# project3_PushButtonLedToggle.net
KiCad netlist of a schematic drawn in Altium Designer
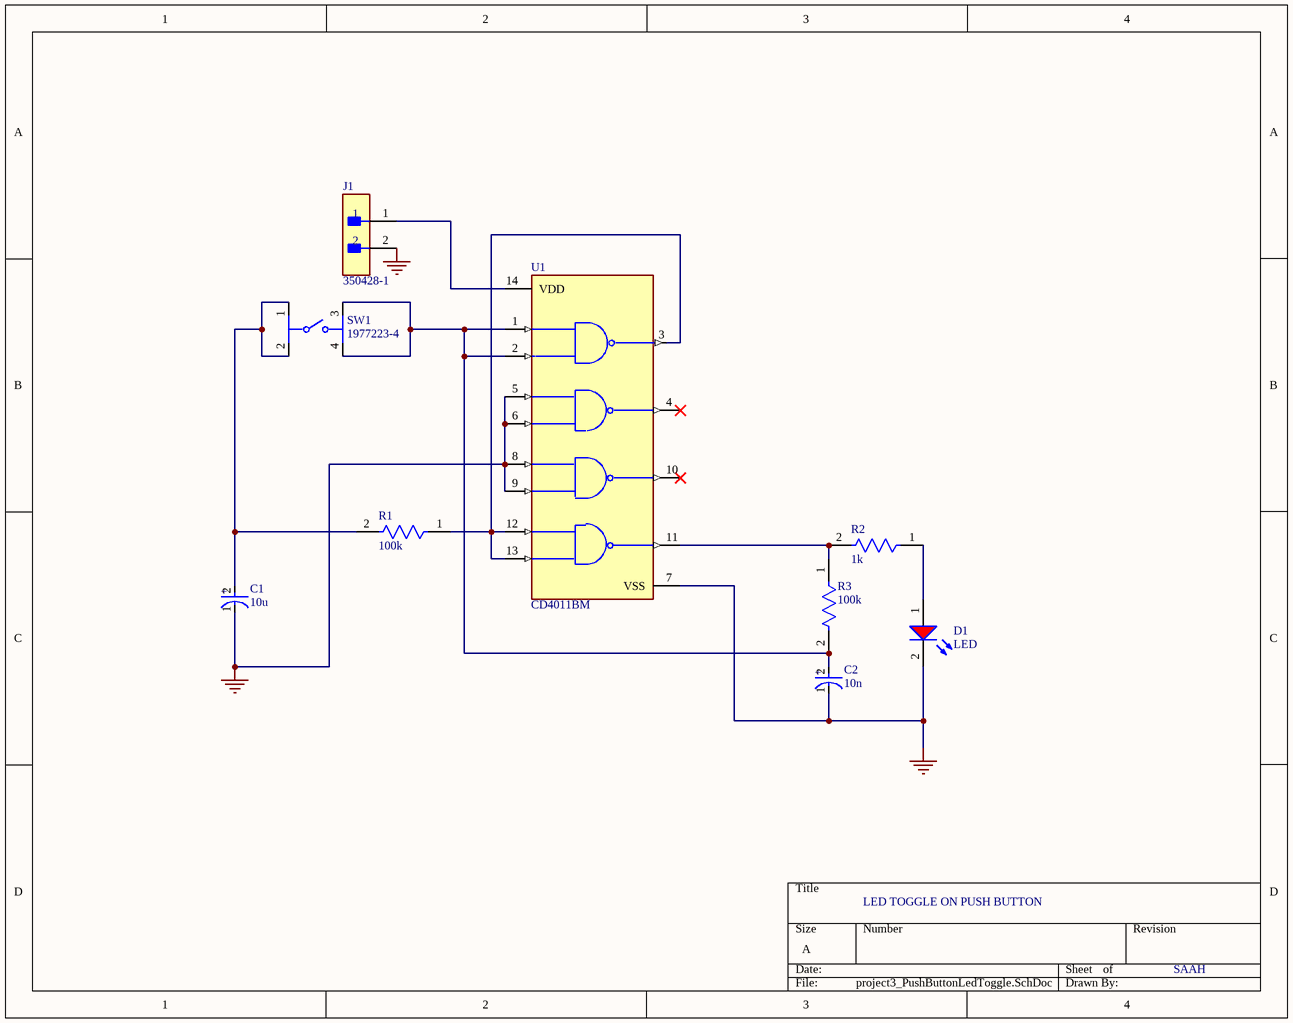
[diagram p0: project3_PushButtonLedToggle.SchDoc]

(export (version "E")
  (design (tool "Eeschema 10.0.6"))
  (components
    (comp (ref "C1")
      (value "10u")
      (footprint "FP-RAD-TH-D_12_5_0_5-L_20-MFG")
      (description "Aluminum Electrolytic Capacitors (Radial Lead Type) 10uF ±20% 450V")
      (fields (field (name "TOLERANCE") "20%") (field (name "VOLTAGE") "450V"))
      (libsource (lib "Altium Content Vault") (part "a00bbbee19879c290e62620ae7e47b1"))
    )
    (comp (ref "C2")
      (value "10n")
      (footprint "FP-RAD-TH-D_12_5_0_5-L_20-MFG")
      (description "Aluminum Electrolytic Capacitors (Radial Lead Type) 10uF ±20% 450V")
      (fields (field (name "TOLERANCE") "20%") (field (name "VOLTAGE") "450V"))
      (libsource (lib "Altium Content Vault") (part "a00bbbee19879c290e62620ae7e47b1"))
    )
    (comp (ref "D1")
      (value "LED")
      (footprint "WL-TMRC_D5.9H8.7")
      (description "151051SS04000 WL-TMRC THT Mono-color Round Color")
      (libsource (lib "Altium Content Vault") (part "LED_Red_1A-2K"))
    )
    (comp (ref "J1")
      (value "350428-1")
      (footprint "FP-350428-1-MFG")
      (description "CONN HEADER VERT 2POS 6.35MM")
      (fields
        (field (name "OCTOPART") "https://octopart.com/350428-1-te+connectivity-46505355")
        (field (name "MANUFACTURER") "TE Connectivity")
      )
      (libsource (lib "Altium Content Vault") (part "3bc925449376181038e59eaffc5286c"))
    )
    (comp (ref "R1")
      (value "100k")
      (footprint "FP-CF14-MFG")
      (description "RES 7.5K OHM 1/4W 5% AXIAL")
      (fields (field (name "TOLERANCE") "5%"))
      (libsource (lib "Altium Content Vault") (part "1029c3af85768c4190bb7ad29bc67b5"))
    )
    (comp (ref "R2")
      (value "1k")
      (footprint "FP-CF14-MFG")
      (description "RES 7.5K OHM 1/4W 5% AXIAL")
      (fields (field (name "TOLERANCE") "5%"))
      (libsource (lib "Altium Content Vault") (part "1029c3af85768c4190bb7ad29bc67b5"))
    )
    (comp (ref "R3")
      (value "100k")
      (footprint "FP-CF14-MFG")
      (description "RES 7.5K OHM 1/4W 5% AXIAL")
      (fields (field (name "TOLERANCE") "5%"))
      (libsource (lib "Altium Content Vault") (part "1029c3af85768c4190bb7ad29bc67b5"))
    )
    (comp (ref "SW1")
      (value "1977223-4")
      (footprint "FP-1977223-4-MFG")
      (description "SWITCH TACTILE SPST-NO 0.05A 12V")
      (libsource (lib "Altium Content Vault") (part "b8895f3f4cefb76e1819d2863dba89b"))
    )
    (comp (ref "U1")
      (value "CD4011BM")
      (footprint "FP-D0014A-MFG")
      (description "IC GATE NAND 4CH 2-INP 14SOIC")
      (fields
        (field (name "OCTOPART") "https://octopart.com/cd4011bm-texas+instruments-16544")
        (field (name "MANUFACTURER") "Texas Instruments")
      )
      (libsource (lib "Altium Content Vault") (part "34aee00f59a36ebc01a0194c7a3f9db"))
    )
  )
  (nets
    (net (code "1") (name "GND") (class "Default")
      (node (ref "C1") (pin "1") (pinfunction "C_1") (pintype "passive"))
      (node (ref "C2") (pin "1") (pinfunction "C_1") (pintype "passive"))
      (node (ref "D1") (pin "2") (pinfunction "K_2") (pintype "passive"))
      (node (ref "J1") (pin "2") (pinfunction "2_2") (pintype "passive"))
      (node (ref "U1") (pin "5") (pinfunction "C_5") (pintype "input"))
      (node (ref "U1") (pin "6") (pinfunction "D_6") (pintype "input"))
      (node (ref "U1") (pin "7") (pinfunction "VSS_7") (pintype "power_in"))
      (node (ref "U1") (pin "8") (pinfunction "E_8") (pintype "input"))
      (node (ref "U1") (pin "9") (pinfunction "F_9") (pintype "input"))
    )
    (net (code "2") (name "Net-(C1-A)") (class "Default")
      (node (ref "C1") (pin "2") (pinfunction "A_2") (pintype "passive"))
      (node (ref "R1") (pin "2") (pinfunction "2_2") (pintype "passive"))
      (node (ref "SW1") (pin "1") (pinfunction "1_1") (pintype "passive"))
      (node (ref "SW1") (pin "2") (pinfunction "2_2") (pintype "passive"))
    )
    (net (code "3") (name "Net-(C2-A)") (class "Default")
      (node (ref "C2") (pin "2") (pinfunction "A_2") (pintype "passive"))
      (node (ref "R3") (pin "2") (pinfunction "2_2") (pintype "passive"))
      (node (ref "SW1") (pin "3") (pinfunction "3_3") (pintype "passive"))
      (node (ref "SW1") (pin "4") (pinfunction "4_4") (pintype "passive"))
      (node (ref "U1") (pin "1") (pinfunction "A_1") (pintype "input"))
      (node (ref "U1") (pin "2") (pinfunction "B_2") (pintype "input"))
    )
    (net (code "4") (name "Net-(D1-A)") (class "Default")
      (node (ref "D1") (pin "1") (pinfunction "A_1") (pintype "passive"))
      (node (ref "R2") (pin "1") (pinfunction "1_1") (pintype "passive"))
    )
    (net (code "5") (name "Net-(U1-G)") (class "Default")
      (node (ref "R1") (pin "1") (pinfunction "1_1") (pintype "passive"))
      (node (ref "U1") (pin "12") (pinfunction "G_12") (pintype "input"))
      (node (ref "U1") (pin "13") (pinfunction "H_13") (pintype "input"))
      (node (ref "U1") (pin "3") (pinfunction "J_3") (pintype "output"))
    )
    (net (code "6") (name "Net-(U1-M)") (class "Default")
      (node (ref "R2") (pin "2") (pinfunction "2_2") (pintype "passive"))
      (node (ref "R3") (pin "1") (pinfunction "1_1") (pintype "passive"))
      (node (ref "U1") (pin "11") (pinfunction "M_11") (pintype "output"))
    )
    (net (code "7") (name "Net-(U1-VDD)") (class "Default")
      (node (ref "J1") (pin "1") (pinfunction "1_1") (pintype "passive"))
      (node (ref "U1") (pin "14") (pinfunction "VDD_14") (pintype "power_in"))
    )
    (net (code "8") (name "unconnected-(U1-K-Pad4)") (class "Default")
      (node (ref "U1") (pin "4") (pinfunction "K_4") (pintype "output+no_connect"))
    )
    (net (code "9") (name "unconnected-(U1-L-Pad10)") (class "Default")
      (node (ref "U1") (pin "10") (pinfunction "L_10") (pintype "output+no_connect"))
    )
  )
)
